# BBMiniPCB5x5.net
KiCad netlist of a schematic drawn in EAGLE
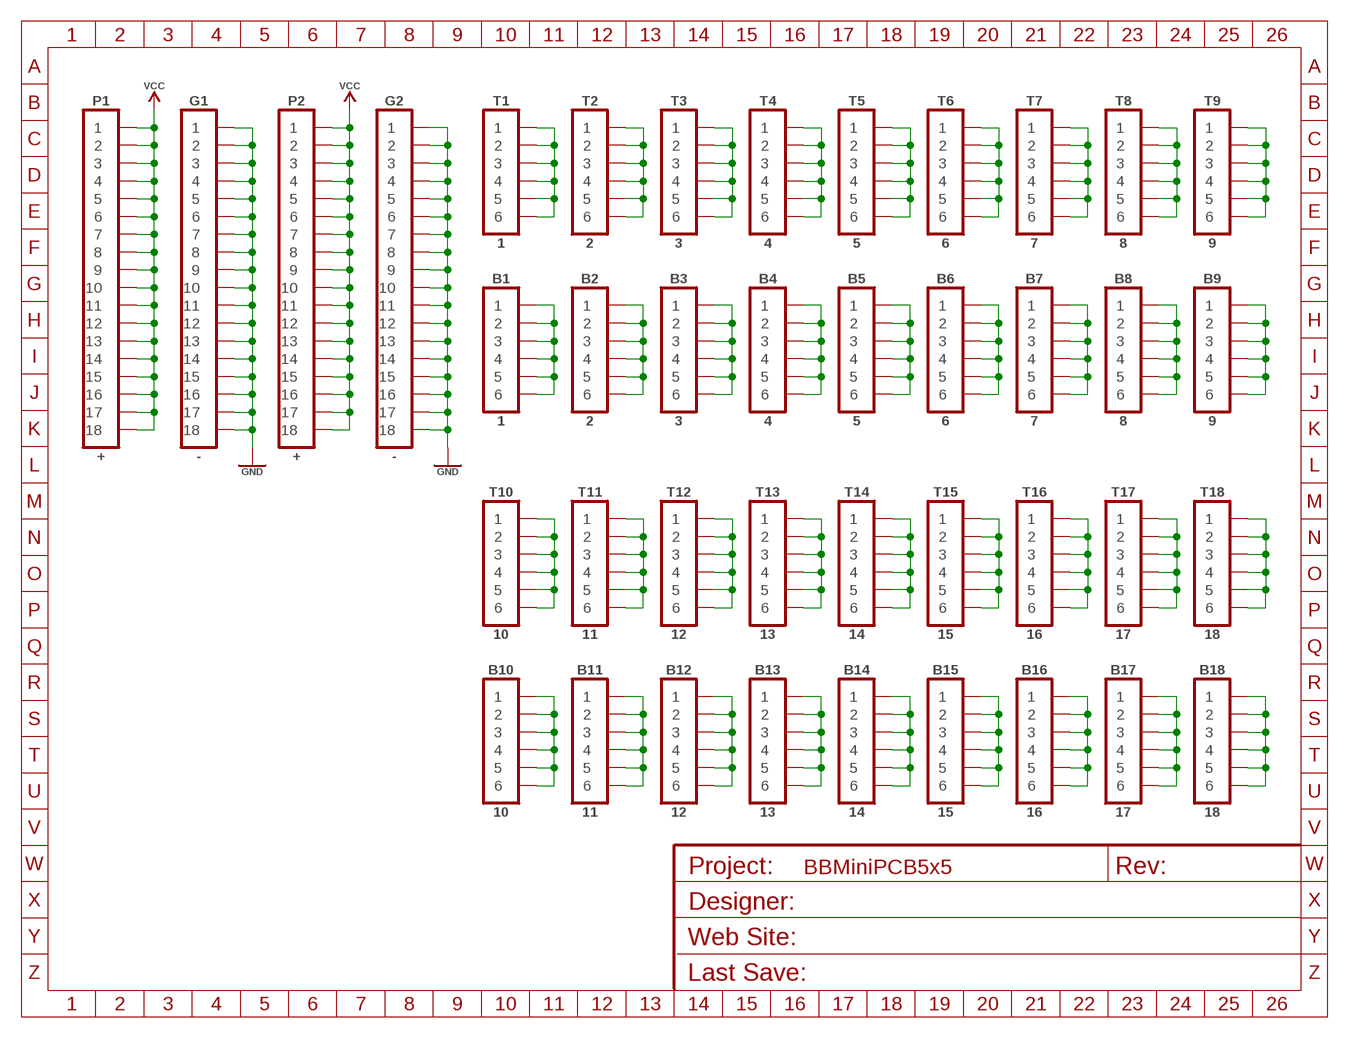
[diagram p0: schematic, sheet 1]

(export (version "E")
  (design (tool "Eeschema 10.0.6"))
  (components
    (comp (ref "B1")
      (value "1")
      (footprint "eagle-import:HDR_1X06_NOSILK")
      (libsource (lib "eagle-import") (part "HDR_1X06_NOSILK"))
    )
    (comp (ref "B2")
      (value "2")
      (footprint "eagle-import:HDR_1X06_NOSILK")
      (libsource (lib "eagle-import") (part "HDR_1X06_NOSILK"))
    )
    (comp (ref "B3")
      (value "3")
      (footprint "eagle-import:HDR_1X06_NOSILK")
      (libsource (lib "eagle-import") (part "HDR_1X06_NOSILK"))
    )
    (comp (ref "B4")
      (value "4")
      (footprint "eagle-import:HDR_1X06_NOSILK")
      (libsource (lib "eagle-import") (part "HDR_1X06_NOSILK"))
    )
    (comp (ref "B5")
      (value "5")
      (footprint "eagle-import:HDR_1X06_NOSILK")
      (libsource (lib "eagle-import") (part "HDR_1X06_NOSILK"))
    )
    (comp (ref "B6")
      (value "6")
      (footprint "eagle-import:HDR_1X06_NOSILK")
      (libsource (lib "eagle-import") (part "HDR_1X06_NOSILK"))
    )
    (comp (ref "B7")
      (value "7")
      (footprint "eagle-import:HDR_1X06_NOSILK")
      (libsource (lib "eagle-import") (part "HDR_1X06_NOSILK"))
    )
    (comp (ref "B8")
      (value "8")
      (footprint "eagle-import:HDR_1X06_NOSILK")
      (libsource (lib "eagle-import") (part "HDR_1X06_NOSILK"))
    )
    (comp (ref "B9")
      (value "9")
      (footprint "eagle-import:HDR_1X06_NOSILK")
      (libsource (lib "eagle-import") (part "HDR_1X06_NOSILK"))
    )
    (comp (ref "B10")
      (value "10")
      (footprint "eagle-import:HDR_1X06_NOSILK")
      (libsource (lib "eagle-import") (part "HDR_1X06_NOSILK"))
    )
    (comp (ref "B11")
      (value "11")
      (footprint "eagle-import:HDR_1X06_NOSILK")
      (libsource (lib "eagle-import") (part "HDR_1X06_NOSILK"))
    )
    (comp (ref "B12")
      (value "12")
      (footprint "eagle-import:HDR_1X06_NOSILK")
      (libsource (lib "eagle-import") (part "HDR_1X06_NOSILK"))
    )
    (comp (ref "B13")
      (value "13")
      (footprint "eagle-import:HDR_1X06_NOSILK")
      (libsource (lib "eagle-import") (part "HDR_1X06_NOSILK"))
    )
    (comp (ref "B14")
      (value "14")
      (footprint "eagle-import:HDR_1X06_NOSILK")
      (libsource (lib "eagle-import") (part "HDR_1X06_NOSILK"))
    )
    (comp (ref "B15")
      (value "15")
      (footprint "eagle-import:HDR_1X06_NOSILK")
      (libsource (lib "eagle-import") (part "HDR_1X06_NOSILK"))
    )
    (comp (ref "B16")
      (value "16")
      (footprint "eagle-import:HDR_1X06_NOSILK")
      (libsource (lib "eagle-import") (part "HDR_1X06_NOSILK"))
    )
    (comp (ref "B17")
      (value "17")
      (footprint "eagle-import:HDR_1X06_NOSILK")
      (libsource (lib "eagle-import") (part "HDR_1X06_NOSILK"))
    )
    (comp (ref "B18")
      (value "18")
      (footprint "eagle-import:HDR_1X06_NOSILK")
      (libsource (lib "eagle-import") (part "HDR_1X06_NOSILK"))
    )
    (comp (ref "G1")
      (value "-")
      (footprint "eagle-import:HDR_1X18_NOSILK")
      (libsource (lib "eagle-import") (part "HDR_1X18_NOSILK"))
    )
    (comp (ref "G2")
      (value "-")
      (footprint "eagle-import:HDR_1X18_NOSILK")
      (libsource (lib "eagle-import") (part "HDR_1X18_NOSILK"))
    )
    (comp (ref "P1")
      (value "+")
      (footprint "eagle-import:HDR_1X18_NOSILK")
      (libsource (lib "eagle-import") (part "HDR_1X18_NOSILK"))
    )
    (comp (ref "P2")
      (value "+")
      (footprint "eagle-import:HDR_1X18_NOSILK")
      (libsource (lib "eagle-import") (part "HDR_1X18_NOSILK"))
    )
    (comp (ref "T1")
      (value "1")
      (footprint "eagle-import:HDR_1X06_NOSILK")
      (libsource (lib "eagle-import") (part "HDR_1X06_NOSILK"))
    )
    (comp (ref "T2")
      (value "2")
      (footprint "eagle-import:HDR_1X06_NOSILK")
      (libsource (lib "eagle-import") (part "HDR_1X06_NOSILK"))
    )
    (comp (ref "T3")
      (value "3")
      (footprint "eagle-import:HDR_1X06_NOSILK")
      (libsource (lib "eagle-import") (part "HDR_1X06_NOSILK"))
    )
    (comp (ref "T4")
      (value "4")
      (footprint "eagle-import:HDR_1X06_NOSILK")
      (libsource (lib "eagle-import") (part "HDR_1X06_NOSILK"))
    )
    (comp (ref "T5")
      (value "5")
      (footprint "eagle-import:HDR_1X06_NOSILK")
      (libsource (lib "eagle-import") (part "HDR_1X06_NOSILK"))
    )
    (comp (ref "T6")
      (value "6")
      (footprint "eagle-import:HDR_1X06_NOSILK")
      (libsource (lib "eagle-import") (part "HDR_1X06_NOSILK"))
    )
    (comp (ref "T7")
      (value "7")
      (footprint "eagle-import:HDR_1X06_NOSILK")
      (libsource (lib "eagle-import") (part "HDR_1X06_NOSILK"))
    )
    (comp (ref "T8")
      (value "8")
      (footprint "eagle-import:HDR_1X06_NOSILK")
      (libsource (lib "eagle-import") (part "HDR_1X06_NOSILK"))
    )
    (comp (ref "T9")
      (value "9")
      (footprint "eagle-import:HDR_1X06_NOSILK")
      (libsource (lib "eagle-import") (part "HDR_1X06_NOSILK"))
    )
    (comp (ref "T10")
      (value "10")
      (footprint "eagle-import:HDR_1X06_NOSILK")
      (libsource (lib "eagle-import") (part "HDR_1X06_NOSILK"))
    )
    (comp (ref "T11")
      (value "11")
      (footprint "eagle-import:HDR_1X06_NOSILK")
      (libsource (lib "eagle-import") (part "HDR_1X06_NOSILK"))
    )
    (comp (ref "T12")
      (value "12")
      (footprint "eagle-import:HDR_1X06_NOSILK")
      (libsource (lib "eagle-import") (part "HDR_1X06_NOSILK"))
    )
    (comp (ref "T13")
      (value "13")
      (footprint "eagle-import:HDR_1X06_NOSILK")
      (libsource (lib "eagle-import") (part "HDR_1X06_NOSILK"))
    )
    (comp (ref "T14")
      (value "14")
      (footprint "eagle-import:HDR_1X06_NOSILK")
      (libsource (lib "eagle-import") (part "HDR_1X06_NOSILK"))
    )
    (comp (ref "T15")
      (value "15")
      (footprint "eagle-import:HDR_1X06_NOSILK")
      (libsource (lib "eagle-import") (part "HDR_1X06_NOSILK"))
    )
    (comp (ref "T16")
      (value "16")
      (footprint "eagle-import:HDR_1X06_NOSILK")
      (libsource (lib "eagle-import") (part "HDR_1X06_NOSILK"))
    )
    (comp (ref "T17")
      (value "17")
      (footprint "eagle-import:HDR_1X06_NOSILK")
      (libsource (lib "eagle-import") (part "HDR_1X06_NOSILK"))
    )
    (comp (ref "T18")
      (value "18")
      (footprint "eagle-import:HDR_1X06_NOSILK")
      (libsource (lib "eagle-import") (part "HDR_1X06_NOSILK"))
    )
  )
  (nets
    (net (code "1") (name "GND") (class "Default")
      (node (ref "G1") (pin "1") (pinfunction "1_1") (pintype "passive"))
      (node (ref "G1") (pin "10") (pinfunction "10_10") (pintype "passive"))
      (node (ref "G1") (pin "11") (pinfunction "11_11") (pintype "passive"))
      (node (ref "G1") (pin "12") (pinfunction "12_12") (pintype "passive"))
      (node (ref "G1") (pin "13") (pinfunction "13_13") (pintype "passive"))
      (node (ref "G1") (pin "14") (pinfunction "14_14") (pintype "passive"))
      (node (ref "G1") (pin "15") (pinfunction "15_15") (pintype "passive"))
      (node (ref "G1") (pin "16") (pinfunction "16_16") (pintype "passive"))
      (node (ref "G1") (pin "17") (pinfunction "17_17") (pintype "passive"))
      (node (ref "G1") (pin "18") (pinfunction "18_18") (pintype "passive"))
      (node (ref "G1") (pin "2") (pinfunction "2_2") (pintype "passive"))
      (node (ref "G1") (pin "3") (pinfunction "3_3") (pintype "passive"))
      (node (ref "G1") (pin "4") (pinfunction "4_4") (pintype "passive"))
      (node (ref "G1") (pin "5") (pinfunction "5_5") (pintype "passive"))
      (node (ref "G1") (pin "6") (pinfunction "6_6") (pintype "passive"))
      (node (ref "G1") (pin "7") (pinfunction "7_7") (pintype "passive"))
      (node (ref "G1") (pin "8") (pinfunction "8_8") (pintype "passive"))
      (node (ref "G1") (pin "9") (pinfunction "9_9") (pintype "passive"))
      (node (ref "G2") (pin "1") (pinfunction "1_1") (pintype "passive"))
      (node (ref "G2") (pin "10") (pinfunction "10_10") (pintype "passive"))
      (node (ref "G2") (pin "11") (pinfunction "11_11") (pintype "passive"))
      (node (ref "G2") (pin "12") (pinfunction "12_12") (pintype "passive"))
      (node (ref "G2") (pin "13") (pinfunction "13_13") (pintype "passive"))
      (node (ref "G2") (pin "14") (pinfunction "14_14") (pintype "passive"))
      (node (ref "G2") (pin "15") (pinfunction "15_15") (pintype "passive"))
      (node (ref "G2") (pin "16") (pinfunction "16_16") (pintype "passive"))
      (node (ref "G2") (pin "17") (pinfunction "17_17") (pintype "passive"))
      (node (ref "G2") (pin "18") (pinfunction "18_18") (pintype "passive"))
      (node (ref "G2") (pin "2") (pinfunction "2_2") (pintype "passive"))
      (node (ref "G2") (pin "3") (pinfunction "3_3") (pintype "passive"))
      (node (ref "G2") (pin "4") (pinfunction "4_4") (pintype "passive"))
      (node (ref "G2") (pin "5") (pinfunction "5_5") (pintype "passive"))
      (node (ref "G2") (pin "6") (pinfunction "6_6") (pintype "passive"))
      (node (ref "G2") (pin "7") (pinfunction "7_7") (pintype "passive"))
      (node (ref "G2") (pin "8") (pinfunction "8_8") (pintype "passive"))
      (node (ref "G2") (pin "9") (pinfunction "9_9") (pintype "passive"))
    )
    (net (code "2") (name "Net-(B1-Pad1)") (class "Default")
      (node (ref "B1") (pin "1") (pinfunction "1_1") (pintype "passive"))
      (node (ref "B1") (pin "2") (pinfunction "2_2") (pintype "passive"))
      (node (ref "B1") (pin "3") (pinfunction "3_3") (pintype "passive"))
      (node (ref "B1") (pin "4") (pinfunction "4_4") (pintype "passive"))
      (node (ref "B1") (pin "5") (pinfunction "5_5") (pintype "passive"))
      (node (ref "B1") (pin "6") (pinfunction "6_6") (pintype "passive"))
    )
    (net (code "3") (name "Net-(B2-Pad1)") (class "Default")
      (node (ref "B2") (pin "1") (pinfunction "1_1") (pintype "passive"))
      (node (ref "B2") (pin "2") (pinfunction "2_2") (pintype "passive"))
      (node (ref "B2") (pin "3") (pinfunction "3_3") (pintype "passive"))
      (node (ref "B2") (pin "4") (pinfunction "4_4") (pintype "passive"))
      (node (ref "B2") (pin "5") (pinfunction "5_5") (pintype "passive"))
      (node (ref "B2") (pin "6") (pinfunction "6_6") (pintype "passive"))
    )
    (net (code "4") (name "Net-(B3-Pad1)") (class "Default")
      (node (ref "B3") (pin "1") (pinfunction "1_1") (pintype "passive"))
      (node (ref "B3") (pin "2") (pinfunction "2_2") (pintype "passive"))
      (node (ref "B3") (pin "3") (pinfunction "3_3") (pintype "passive"))
      (node (ref "B3") (pin "4") (pinfunction "4_4") (pintype "passive"))
      (node (ref "B3") (pin "5") (pinfunction "5_5") (pintype "passive"))
      (node (ref "B3") (pin "6") (pinfunction "6_6") (pintype "passive"))
    )
    (net (code "5") (name "Net-(B4-Pad1)") (class "Default")
      (node (ref "B4") (pin "1") (pinfunction "1_1") (pintype "passive"))
      (node (ref "B4") (pin "2") (pinfunction "2_2") (pintype "passive"))
      (node (ref "B4") (pin "3") (pinfunction "3_3") (pintype "passive"))
      (node (ref "B4") (pin "4") (pinfunction "4_4") (pintype "passive"))
      (node (ref "B4") (pin "5") (pinfunction "5_5") (pintype "passive"))
      (node (ref "B4") (pin "6") (pinfunction "6_6") (pintype "passive"))
    )
    (net (code "6") (name "Net-(B5-Pad1)") (class "Default")
      (node (ref "B5") (pin "1") (pinfunction "1_1") (pintype "passive"))
      (node (ref "B5") (pin "2") (pinfunction "2_2") (pintype "passive"))
      (node (ref "B5") (pin "3") (pinfunction "3_3") (pintype "passive"))
      (node (ref "B5") (pin "4") (pinfunction "4_4") (pintype "passive"))
      (node (ref "B5") (pin "5") (pinfunction "5_5") (pintype "passive"))
      (node (ref "B5") (pin "6") (pinfunction "6_6") (pintype "passive"))
    )
    (net (code "7") (name "Net-(B6-Pad1)") (class "Default")
      (node (ref "B6") (pin "1") (pinfunction "1_1") (pintype "passive"))
      (node (ref "B6") (pin "2") (pinfunction "2_2") (pintype "passive"))
      (node (ref "B6") (pin "3") (pinfunction "3_3") (pintype "passive"))
      (node (ref "B6") (pin "4") (pinfunction "4_4") (pintype "passive"))
      (node (ref "B6") (pin "5") (pinfunction "5_5") (pintype "passive"))
      (node (ref "B6") (pin "6") (pinfunction "6_6") (pintype "passive"))
    )
    (net (code "8") (name "Net-(B7-Pad1)") (class "Default")
      (node (ref "B7") (pin "1") (pinfunction "1_1") (pintype "passive"))
      (node (ref "B7") (pin "2") (pinfunction "2_2") (pintype "passive"))
      (node (ref "B7") (pin "3") (pinfunction "3_3") (pintype "passive"))
      (node (ref "B7") (pin "4") (pinfunction "4_4") (pintype "passive"))
      (node (ref "B7") (pin "5") (pinfunction "5_5") (pintype "passive"))
      (node (ref "B7") (pin "6") (pinfunction "6_6") (pintype "passive"))
    )
    (net (code "9") (name "Net-(B8-Pad1)") (class "Default")
      (node (ref "B8") (pin "1") (pinfunction "1_1") (pintype "passive"))
      (node (ref "B8") (pin "2") (pinfunction "2_2") (pintype "passive"))
      (node (ref "B8") (pin "3") (pinfunction "3_3") (pintype "passive"))
      (node (ref "B8") (pin "4") (pinfunction "4_4") (pintype "passive"))
      (node (ref "B8") (pin "5") (pinfunction "5_5") (pintype "passive"))
      (node (ref "B8") (pin "6") (pinfunction "6_6") (pintype "passive"))
    )
    (net (code "10") (name "Net-(B9-Pad1)") (class "Default")
      (node (ref "B9") (pin "1") (pinfunction "1_1") (pintype "passive"))
      (node (ref "B9") (pin "2") (pinfunction "2_2") (pintype "passive"))
      (node (ref "B9") (pin "3") (pinfunction "3_3") (pintype "passive"))
      (node (ref "B9") (pin "4") (pinfunction "4_4") (pintype "passive"))
      (node (ref "B9") (pin "5") (pinfunction "5_5") (pintype "passive"))
      (node (ref "B9") (pin "6") (pinfunction "6_6") (pintype "passive"))
    )
    (net (code "11") (name "Net-(B10-Pad1)") (class "Default")
      (node (ref "B10") (pin "1") (pinfunction "1_1") (pintype "passive"))
      (node (ref "B10") (pin "2") (pinfunction "2_2") (pintype "passive"))
      (node (ref "B10") (pin "3") (pinfunction "3_3") (pintype "passive"))
      (node (ref "B10") (pin "4") (pinfunction "4_4") (pintype "passive"))
      (node (ref "B10") (pin "5") (pinfunction "5_5") (pintype "passive"))
      (node (ref "B10") (pin "6") (pinfunction "6_6") (pintype "passive"))
    )
    (net (code "12") (name "Net-(B11-Pad1)") (class "Default")
      (node (ref "B11") (pin "1") (pinfunction "1_1") (pintype "passive"))
      (node (ref "B11") (pin "2") (pinfunction "2_2") (pintype "passive"))
      (node (ref "B11") (pin "3") (pinfunction "3_3") (pintype "passive"))
      (node (ref "B11") (pin "4") (pinfunction "4_4") (pintype "passive"))
      (node (ref "B11") (pin "5") (pinfunction "5_5") (pintype "passive"))
      (node (ref "B11") (pin "6") (pinfunction "6_6") (pintype "passive"))
    )
    (net (code "13") (name "Net-(B12-Pad1)") (class "Default")
      (node (ref "B12") (pin "1") (pinfunction "1_1") (pintype "passive"))
      (node (ref "B12") (pin "2") (pinfunction "2_2") (pintype "passive"))
      (node (ref "B12") (pin "3") (pinfunction "3_3") (pintype "passive"))
      (node (ref "B12") (pin "4") (pinfunction "4_4") (pintype "passive"))
      (node (ref "B12") (pin "5") (pinfunction "5_5") (pintype "passive"))
      (node (ref "B12") (pin "6") (pinfunction "6_6") (pintype "passive"))
    )
    (net (code "14") (name "Net-(B13-Pad1)") (class "Default")
      (node (ref "B13") (pin "1") (pinfunction "1_1") (pintype "passive"))
      (node (ref "B13") (pin "2") (pinfunction "2_2") (pintype "passive"))
      (node (ref "B13") (pin "3") (pinfunction "3_3") (pintype "passive"))
      (node (ref "B13") (pin "4") (pinfunction "4_4") (pintype "passive"))
      (node (ref "B13") (pin "5") (pinfunction "5_5") (pintype "passive"))
      (node (ref "B13") (pin "6") (pinfunction "6_6") (pintype "passive"))
    )
    (net (code "15") (name "Net-(B14-Pad1)") (class "Default")
      (node (ref "B14") (pin "1") (pinfunction "1_1") (pintype "passive"))
      (node (ref "B14") (pin "2") (pinfunction "2_2") (pintype "passive"))
      (node (ref "B14") (pin "3") (pinfunction "3_3") (pintype "passive"))
      (node (ref "B14") (pin "4") (pinfunction "4_4") (pintype "passive"))
      (node (ref "B14") (pin "5") (pinfunction "5_5") (pintype "passive"))
      (node (ref "B14") (pin "6") (pinfunction "6_6") (pintype "passive"))
    )
    (net (code "16") (name "Net-(B15-Pad1)") (class "Default")
      (node (ref "B15") (pin "1") (pinfunction "1_1") (pintype "passive"))
      (node (ref "B15") (pin "2") (pinfunction "2_2") (pintype "passive"))
      (node (ref "B15") (pin "3") (pinfunction "3_3") (pintype "passive"))
      (node (ref "B15") (pin "4") (pinfunction "4_4") (pintype "passive"))
      (node (ref "B15") (pin "5") (pinfunction "5_5") (pintype "passive"))
      (node (ref "B15") (pin "6") (pinfunction "6_6") (pintype "passive"))
    )
    (net (code "17") (name "Net-(B16-Pad1)") (class "Default")
      (node (ref "B16") (pin "1") (pinfunction "1_1") (pintype "passive"))
      (node (ref "B16") (pin "2") (pinfunction "2_2") (pintype "passive"))
      (node (ref "B16") (pin "3") (pinfunction "3_3") (pintype "passive"))
      (node (ref "B16") (pin "4") (pinfunction "4_4") (pintype "passive"))
      (node (ref "B16") (pin "5") (pinfunction "5_5") (pintype "passive"))
      (node (ref "B16") (pin "6") (pinfunction "6_6") (pintype "passive"))
    )
    (net (code "18") (name "Net-(B17-Pad1)") (class "Default")
      (node (ref "B17") (pin "1") (pinfunction "1_1") (pintype "passive"))
      (node (ref "B17") (pin "2") (pinfunction "2_2") (pintype "passive"))
      (node (ref "B17") (pin "3") (pinfunction "3_3") (pintype "passive"))
      (node (ref "B17") (pin "4") (pinfunction "4_4") (pintype "passive"))
      (node (ref "B17") (pin "5") (pinfunction "5_5") (pintype "passive"))
      (node (ref "B17") (pin "6") (pinfunction "6_6") (pintype "passive"))
    )
    (net (code "19") (name "Net-(B18-Pad1)") (class "Default")
      (node (ref "B18") (pin "1") (pinfunction "1_1") (pintype "passive"))
      (node (ref "B18") (pin "2") (pinfunction "2_2") (pintype "passive"))
      (node (ref "B18") (pin "3") (pinfunction "3_3") (pintype "passive"))
      (node (ref "B18") (pin "4") (pinfunction "4_4") (pintype "passive"))
      (node (ref "B18") (pin "5") (pinfunction "5_5") (pintype "passive"))
      (node (ref "B18") (pin "6") (pinfunction "6_6") (pintype "passive"))
    )
    (net (code "20") (name "Net-(T1-Pad1)") (class "Default")
      (node (ref "T1") (pin "1") (pinfunction "1_1") (pintype "passive"))
      (node (ref "T1") (pin "2") (pinfunction "2_2") (pintype "passive"))
      (node (ref "T1") (pin "3") (pinfunction "3_3") (pintype "passive"))
      (node (ref "T1") (pin "4") (pinfunction "4_4") (pintype "passive"))
      (node (ref "T1") (pin "5") (pinfunction "5_5") (pintype "passive"))
      (node (ref "T1") (pin "6") (pinfunction "6_6") (pintype "passive"))
    )
    (net (code "21") (name "Net-(T2-Pad1)") (class "Default")
      (node (ref "T2") (pin "1") (pinfunction "1_1") (pintype "passive"))
      (node (ref "T2") (pin "2") (pinfunction "2_2") (pintype "passive"))
      (node (ref "T2") (pin "3") (pinfunction "3_3") (pintype "passive"))
      (node (ref "T2") (pin "4") (pinfunction "4_4") (pintype "passive"))
      (node (ref "T2") (pin "5") (pinfunction "5_5") (pintype "passive"))
      (node (ref "T2") (pin "6") (pinfunction "6_6") (pintype "passive"))
    )
    (net (code "22") (name "Net-(T3-Pad1)") (class "Default")
      (node (ref "T3") (pin "1") (pinfunction "1_1") (pintype "passive"))
      (node (ref "T3") (pin "2") (pinfunction "2_2") (pintype "passive"))
      (node (ref "T3") (pin "3") (pinfunction "3_3") (pintype "passive"))
      (node (ref "T3") (pin "4") (pinfunction "4_4") (pintype "passive"))
      (node (ref "T3") (pin "5") (pinfunction "5_5") (pintype "passive"))
      (node (ref "T3") (pin "6") (pinfunction "6_6") (pintype "passive"))
    )
    (net (code "23") (name "Net-(T4-Pad1)") (class "Default")
      (node (ref "T4") (pin "1") (pinfunction "1_1") (pintype "passive"))
      (node (ref "T4") (pin "2") (pinfunction "2_2") (pintype "passive"))
      (node (ref "T4") (pin "3") (pinfunction "3_3") (pintype "passive"))
      (node (ref "T4") (pin "4") (pinfunction "4_4") (pintype "passive"))
      (node (ref "T4") (pin "5") (pinfunction "5_5") (pintype "passive"))
      (node (ref "T4") (pin "6") (pinfunction "6_6") (pintype "passive"))
    )
    (net (code "24") (name "Net-(T5-Pad1)") (class "Default")
      (node (ref "T5") (pin "1") (pinfunction "1_1") (pintype "passive"))
      (node (ref "T5") (pin "2") (pinfunction "2_2") (pintype "passive"))
      (node (ref "T5") (pin "3") (pinfunction "3_3") (pintype "passive"))
      (node (ref "T5") (pin "4") (pinfunction "4_4") (pintype "passive"))
      (node (ref "T5") (pin "5") (pinfunction "5_5") (pintype "passive"))
      (node (ref "T5") (pin "6") (pinfunction "6_6") (pintype "passive"))
    )
    (net (code "25") (name "Net-(T6-Pad1)") (class "Default")
      (node (ref "T6") (pin "1") (pinfunction "1_1") (pintype "passive"))
      (node (ref "T6") (pin "2") (pinfunction "2_2") (pintype "passive"))
      (node (ref "T6") (pin "3") (pinfunction "3_3") (pintype "passive"))
      (node (ref "T6") (pin "4") (pinfunction "4_4") (pintype "passive"))
      (node (ref "T6") (pin "5") (pinfunction "5_5") (pintype "passive"))
      (node (ref "T6") (pin "6") (pinfunction "6_6") (pintype "passive"))
    )
    (net (code "26") (name "Net-(T7-Pad1)") (class "Default")
      (node (ref "T7") (pin "1") (pinfunction "1_1") (pintype "passive"))
      (node (ref "T7") (pin "2") (pinfunction "2_2") (pintype "passive"))
      (node (ref "T7") (pin "3") (pinfunction "3_3") (pintype "passive"))
      (node (ref "T7") (pin "4") (pinfunction "4_4") (pintype "passive"))
      (node (ref "T7") (pin "5") (pinfunction "5_5") (pintype "passive"))
      (node (ref "T7") (pin "6") (pinfunction "6_6") (pintype "passive"))
    )
    (net (code "27") (name "Net-(T8-Pad1)") (class "Default")
      (node (ref "T8") (pin "1") (pinfunction "1_1") (pintype "passive"))
      (node (ref "T8") (pin "2") (pinfunction "2_2") (pintype "passive"))
      (node (ref "T8") (pin "3") (pinfunction "3_3") (pintype "passive"))
      (node (ref "T8") (pin "4") (pinfunction "4_4") (pintype "passive"))
      (node (ref "T8") (pin "5") (pinfunction "5_5") (pintype "passive"))
      (node (ref "T8") (pin "6") (pinfunction "6_6") (pintype "passive"))
    )
    (net (code "28") (name "Net-(T9-Pad1)") (class "Default")
      (node (ref "T9") (pin "1") (pinfunction "1_1") (pintype "passive"))
      (node (ref "T9") (pin "2") (pinfunction "2_2") (pintype "passive"))
      (node (ref "T9") (pin "3") (pinfunction "3_3") (pintype "passive"))
      (node (ref "T9") (pin "4") (pinfunction "4_4") (pintype "passive"))
      (node (ref "T9") (pin "5") (pinfunction "5_5") (pintype "passive"))
      (node (ref "T9") (pin "6") (pinfunction "6_6") (pintype "passive"))
    )
    (net (code "29") (name "Net-(T10-Pad1)") (class "Default")
      (node (ref "T10") (pin "1") (pinfunction "1_1") (pintype "passive"))
      (node (ref "T10") (pin "2") (pinfunction "2_2") (pintype "passive"))
      (node (ref "T10") (pin "3") (pinfunction "3_3") (pintype "passive"))
      (node (ref "T10") (pin "4") (pinfunction "4_4") (pintype "passive"))
      (node (ref "T10") (pin "5") (pinfunction "5_5") (pintype "passive"))
      (node (ref "T10") (pin "6") (pinfunction "6_6") (pintype "passive"))
    )
    (net (code "30") (name "Net-(T11-Pad1)") (class "Default")
      (node (ref "T11") (pin "1") (pinfunction "1_1") (pintype "passive"))
      (node (ref "T11") (pin "2") (pinfunction "2_2") (pintype "passive"))
      (node (ref "T11") (pin "3") (pinfunction "3_3") (pintype "passive"))
      (node (ref "T11") (pin "4") (pinfunction "4_4") (pintype "passive"))
      (node (ref "T11") (pin "5") (pinfunction "5_5") (pintype "passive"))
      (node (ref "T11") (pin "6") (pinfunction "6_6") (pintype "passive"))
    )
    (net (code "31") (name "Net-(T12-Pad1)") (class "Default")
      (node (ref "T12") (pin "1") (pinfunction "1_1") (pintype "passive"))
      (node (ref "T12") (pin "2") (pinfunction "2_2") (pintype "passive"))
      (node (ref "T12") (pin "3") (pinfunction "3_3") (pintype "passive"))
      (node (ref "T12") (pin "4") (pinfunction "4_4") (pintype "passive"))
      (node (ref "T12") (pin "5") (pinfunction "5_5") (pintype "passive"))
      (node (ref "T12") (pin "6") (pinfunction "6_6") (pintype "passive"))
    )
    (net (code "32") (name "Net-(T13-Pad1)") (class "Default")
      (node (ref "T13") (pin "1") (pinfunction "1_1") (pintype "passive"))
      (node (ref "T13") (pin "2") (pinfunction "2_2") (pintype "passive"))
      (node (ref "T13") (pin "3") (pinfunction "3_3") (pintype "passive"))
      (node (ref "T13") (pin "4") (pinfunction "4_4") (pintype "passive"))
      (node (ref "T13") (pin "5") (pinfunction "5_5") (pintype "passive"))
      (node (ref "T13") (pin "6") (pinfunction "6_6") (pintype "passive"))
    )
    (net (code "33") (name "Net-(T14-Pad1)") (class "Default")
      (node (ref "T14") (pin "1") (pinfunction "1_1") (pintype "passive"))
      (node (ref "T14") (pin "2") (pinfunction "2_2") (pintype "passive"))
      (node (ref "T14") (pin "3") (pinfunction "3_3") (pintype "passive"))
      (node (ref "T14") (pin "4") (pinfunction "4_4") (pintype "passive"))
      (node (ref "T14") (pin "5") (pinfunction "5_5") (pintype "passive"))
      (node (ref "T14") (pin "6") (pinfunction "6_6") (pintype "passive"))
    )
    (net (code "34") (name "Net-(T15-Pad1)") (class "Default")
      (node (ref "T15") (pin "1") (pinfunction "1_1") (pintype "passive"))
      (node (ref "T15") (pin "2") (pinfunction "2_2") (pintype "passive"))
      (node (ref "T15") (pin "3") (pinfunction "3_3") (pintype "passive"))
      (node (ref "T15") (pin "4") (pinfunction "4_4") (pintype "passive"))
      (node (ref "T15") (pin "5") (pinfunction "5_5") (pintype "passive"))
      (node (ref "T15") (pin "6") (pinfunction "6_6") (pintype "passive"))
    )
    (net (code "35") (name "Net-(T16-Pad1)") (class "Default")
      (node (ref "T16") (pin "1") (pinfunction "1_1") (pintype "passive"))
      (node (ref "T16") (pin "2") (pinfunction "2_2") (pintype "passive"))
      (node (ref "T16") (pin "3") (pinfunction "3_3") (pintype "passive"))
      (node (ref "T16") (pin "4") (pinfunction "4_4") (pintype "passive"))
      (node (ref "T16") (pin "5") (pinfunction "5_5") (pintype "passive"))
      (node (ref "T16") (pin "6") (pinfunction "6_6") (pintype "passive"))
    )
    (net (code "36") (name "Net-(T17-Pad1)") (class "Default")
      (node (ref "T17") (pin "1") (pinfunction "1_1") (pintype "passive"))
      (node (ref "T17") (pin "2") (pinfunction "2_2") (pintype "passive"))
      (node (ref "T17") (pin "3") (pinfunction "3_3") (pintype "passive"))
      (node (ref "T17") (pin "4") (pinfunction "4_4") (pintype "passive"))
      (node (ref "T17") (pin "5") (pinfunction "5_5") (pintype "passive"))
      (node (ref "T17") (pin "6") (pinfunction "6_6") (pintype "passive"))
    )
    (net (code "37") (name "Net-(T18-Pad1)") (class "Default")
      (node (ref "T18") (pin "1") (pinfunction "1_1") (pintype "passive"))
      (node (ref "T18") (pin "2") (pinfunction "2_2") (pintype "passive"))
      (node (ref "T18") (pin "3") (pinfunction "3_3") (pintype "passive"))
      (node (ref "T18") (pin "4") (pinfunction "4_4") (pintype "passive"))
      (node (ref "T18") (pin "5") (pinfunction "5_5") (pintype "passive"))
      (node (ref "T18") (pin "6") (pinfunction "6_6") (pintype "passive"))
    )
    (net (code "38") (name "VCC") (class "Default")
      (node (ref "P1") (pin "1") (pinfunction "1_1") (pintype "passive"))
      (node (ref "P1") (pin "10") (pinfunction "10_10") (pintype "passive"))
      (node (ref "P1") (pin "11") (pinfunction "11_11") (pintype "passive"))
      (node (ref "P1") (pin "12") (pinfunction "12_12") (pintype "passive"))
      (node (ref "P1") (pin "13") (pinfunction "13_13") (pintype "passive"))
      (node (ref "P1") (pin "14") (pinfunction "14_14") (pintype "passive"))
      (node (ref "P1") (pin "15") (pinfunction "15_15") (pintype "passive"))
      (node (ref "P1") (pin "16") (pinfunction "16_16") (pintype "passive"))
      (node (ref "P1") (pin "17") (pinfunction "17_17") (pintype "passive"))
      (node (ref "P1") (pin "18") (pinfunction "18_18") (pintype "passive"))
      (node (ref "P1") (pin "2") (pinfunction "2_2") (pintype "passive"))
      (node (ref "P1") (pin "3") (pinfunction "3_3") (pintype "passive"))
      (node (ref "P1") (pin "4") (pinfunction "4_4") (pintype "passive"))
      (node (ref "P1") (pin "5") (pinfunction "5_5") (pintype "passive"))
      (node (ref "P1") (pin "6") (pinfunction "6_6") (pintype "passive"))
      (node (ref "P1") (pin "7") (pinfunction "7_7") (pintype "passive"))
      (node (ref "P1") (pin "8") (pinfunction "8_8") (pintype "passive"))
      (node (ref "P1") (pin "9") (pinfunction "9_9") (pintype "passive"))
      (node (ref "P2") (pin "1") (pinfunction "1_1") (pintype "passive"))
      (node (ref "P2") (pin "10") (pinfunction "10_10") (pintype "passive"))
      (node (ref "P2") (pin "11") (pinfunction "11_11") (pintype "passive"))
      (node (ref "P2") (pin "12") (pinfunction "12_12") (pintype "passive"))
      (node (ref "P2") (pin "13") (pinfunction "13_13") (pintype "passive"))
      (node (ref "P2") (pin "14") (pinfunction "14_14") (pintype "passive"))
      (node (ref "P2") (pin "15") (pinfunction "15_15") (pintype "passive"))
      (node (ref "P2") (pin "16") (pinfunction "16_16") (pintype "passive"))
      (node (ref "P2") (pin "17") (pinfunction "17_17") (pintype "passive"))
      (node (ref "P2") (pin "18") (pinfunction "18_18") (pintype "passive"))
      (node (ref "P2") (pin "2") (pinfunction "2_2") (pintype "passive"))
      (node (ref "P2") (pin "3") (pinfunction "3_3") (pintype "passive"))
      (node (ref "P2") (pin "4") (pinfunction "4_4") (pintype "passive"))
      (node (ref "P2") (pin "5") (pinfunction "5_5") (pintype "passive"))
      (node (ref "P2") (pin "6") (pinfunction "6_6") (pintype "passive"))
      (node (ref "P2") (pin "7") (pinfunction "7_7") (pintype "passive"))
      (node (ref "P2") (pin "8") (pinfunction "8_8") (pintype "passive"))
      (node (ref "P2") (pin "9") (pinfunction "9_9") (pintype "passive"))
    )
  )
)
